# mcu.net
KiCad netlist of a schematic drawn in Altium Designer
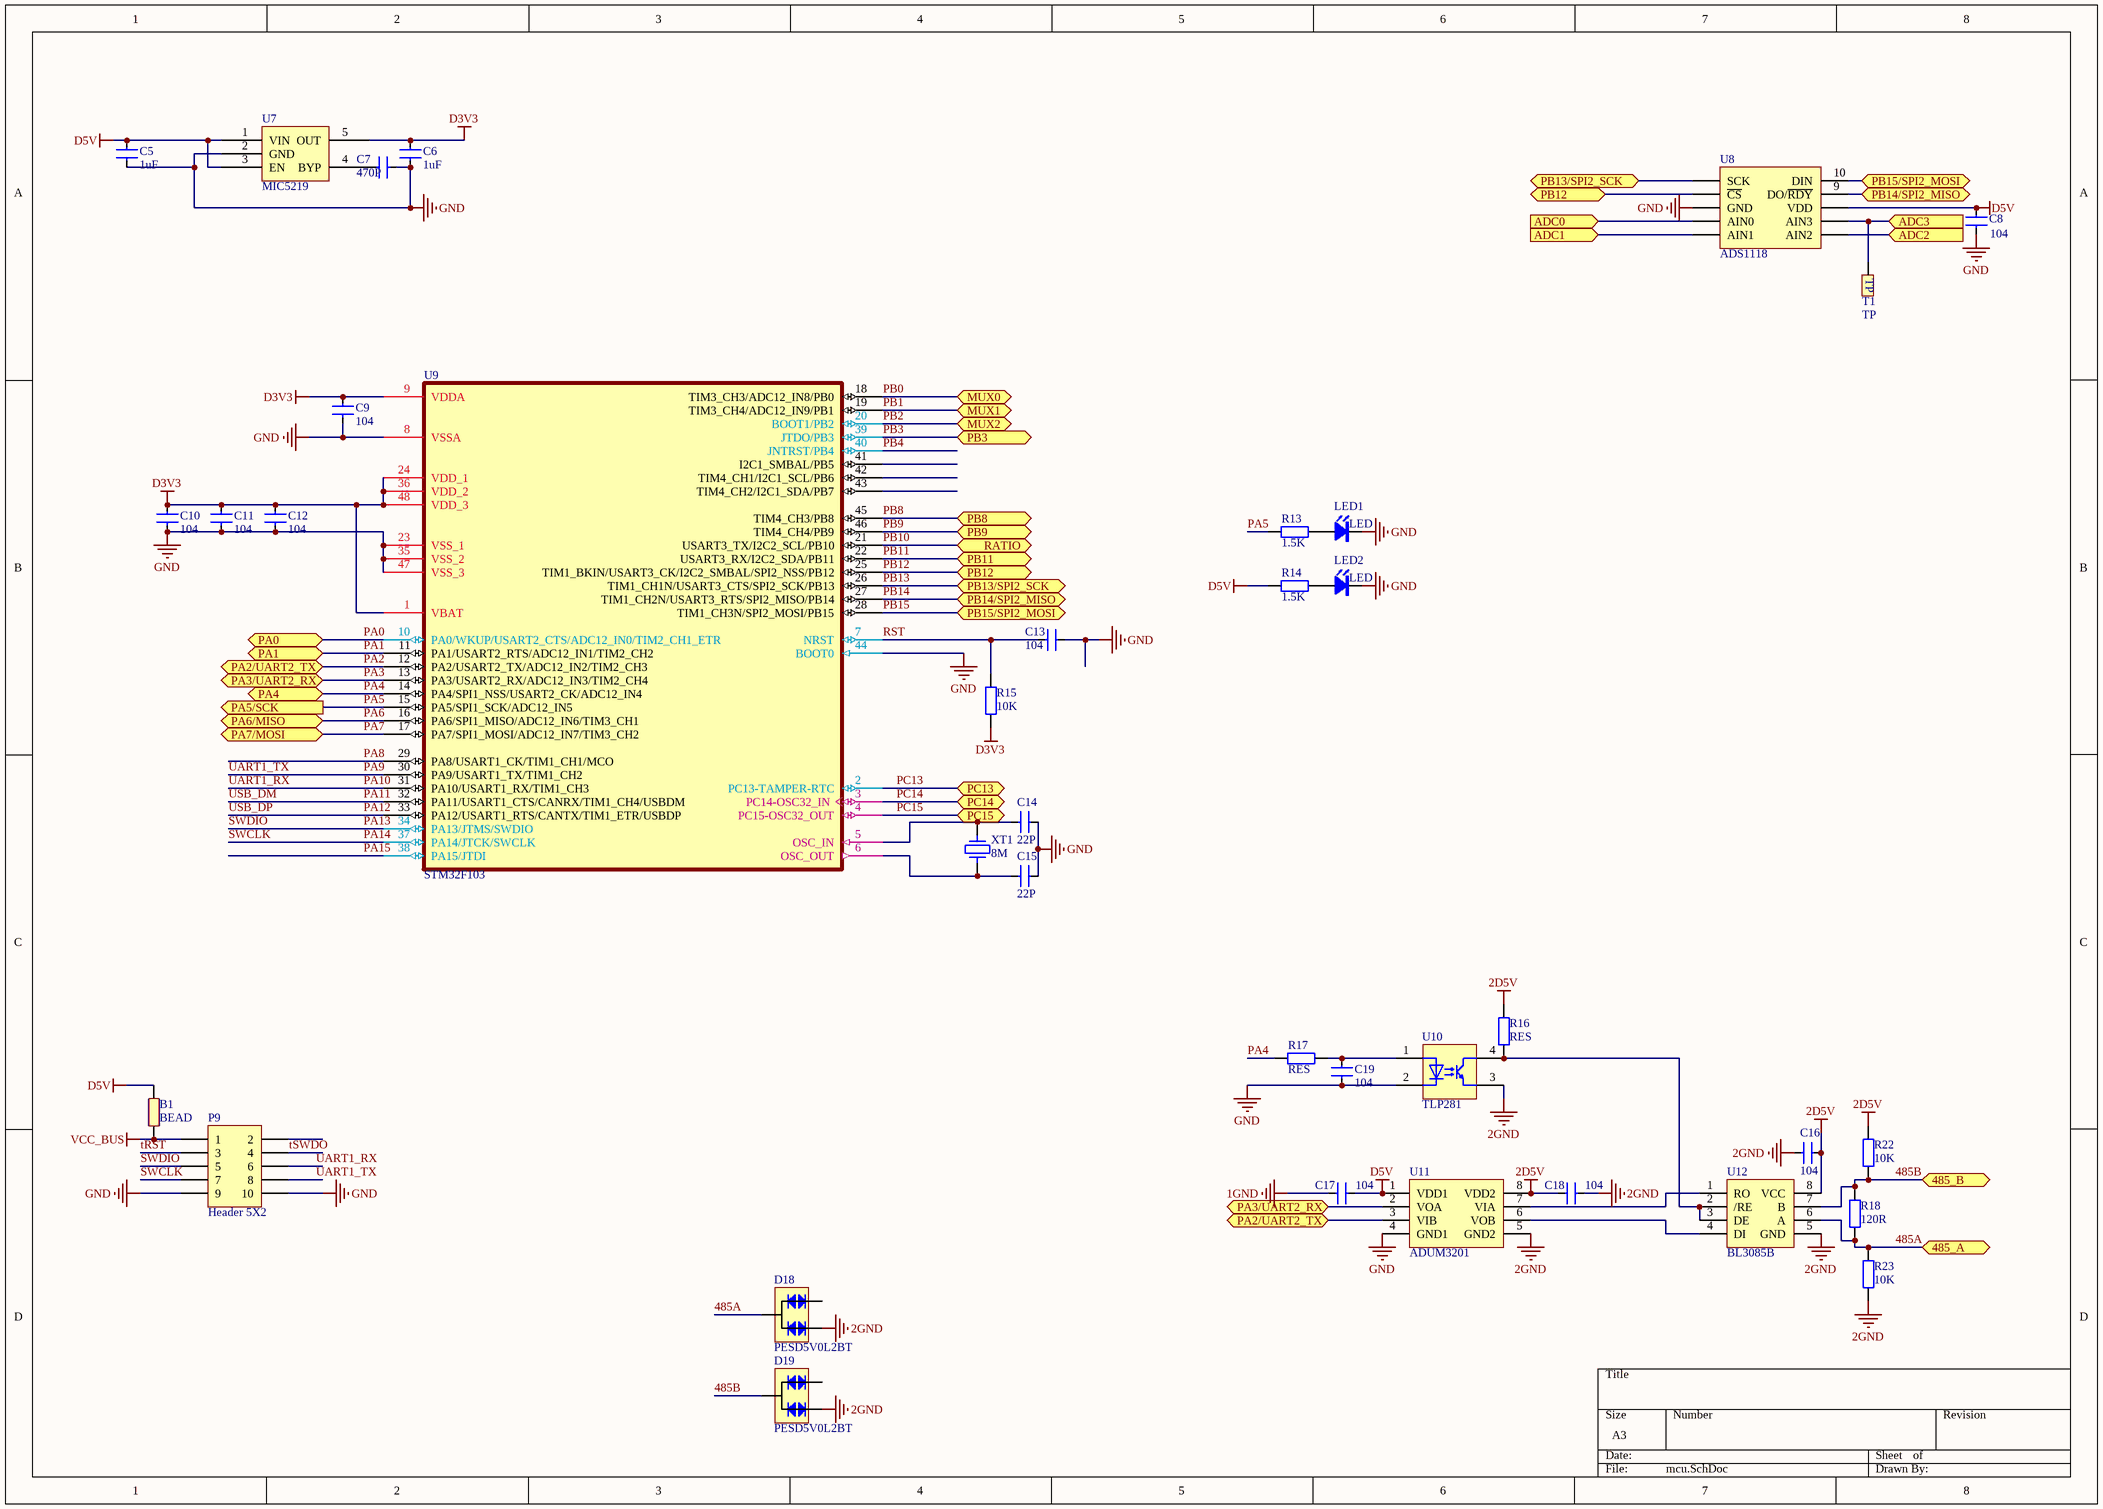
[diagram p0: mcu.SchDoc]

(export (version "E")
  (design (tool "Eeschema 10.0.6"))
  (components
    (comp (ref "B1")
      (value "BEAD")
      (footprint "0603L")
      (description "磁珠")
      (libsource (lib "lib_AD") (part "BEAD"))
    )
    (comp (ref "C5")
      (value "1uF")
      (footprint "0805C")
      (description "普通小电容")
      (libsource (lib "") (part "CAP_1"))
    )
    (comp (ref "C6")
      (value "1uF")
      (footprint "0805C")
      (description "普通小电容")
      (libsource (lib "") (part "CAP_1"))
    )
    (comp (ref "C7")
      (value "470P")
      (footprint "0603C")
      (description "普通小电容")
      (libsource (lib "lib_GMDZ") (part "CAP"))
    )
    (comp (ref "C8")
      (value "104")
      (footprint "0603C")
      (description "普通小电容")
      (libsource (lib "") (part "CAP_1"))
    )
    (comp (ref "C9")
      (value "104")
      (footprint "0603C")
      (description "普通小电容")
      (libsource (lib "lib_GMDZ") (part "CAP"))
    )
    (comp (ref "C10")
      (value "104")
      (footprint "0603C")
      (description "普通小电容")
      (libsource (lib "lib_GMDZ") (part "CAP"))
    )
    (comp (ref "C11")
      (value "104")
      (footprint "0603C")
      (description "普通小电容")
      (libsource (lib "lib_GMDZ") (part "CAP"))
    )
    (comp (ref "C12")
      (value "104")
      (footprint "0603C")
      (description "普通小电容")
      (libsource (lib "lib_GMDZ") (part "CAP"))
    )
    (comp (ref "C13")
      (value "104")
      (footprint "0603C")
      (description "普通小电容")
      (libsource (lib "lib_AD") (part "CAP"))
    )
    (comp (ref "C14")
      (value "22P")
      (footprint "0603C")
      (description "普通小电容")
      (libsource (lib "lib_AD") (part "CAP"))
    )
    (comp (ref "C15")
      (value "22P")
      (footprint "0603C")
      (description "普通小电容")
      (libsource (lib "lib_AD") (part "CAP"))
    )
    (comp (ref "C16")
      (value "104")
      (footprint "0603C")
      (description "普通小电容")
      (libsource (lib "lib_AD") (part "CAP"))
    )
    (comp (ref "C17")
      (value "104")
      (footprint "0603C")
      (description "普通小电容")
      (libsource (lib "lib_AD") (part "CAP"))
    )
    (comp (ref "C18")
      (value "104")
      (footprint "0603C")
      (description "普通小电容")
      (libsource (lib "lib_AD") (part "CAP"))
    )
    (comp (ref "C19")
      (value "104")
      (footprint "0603C")
      (description "普通小电容")
      (libsource (lib "lib_AD") (part "CAP"))
    )
    (comp (ref "D18")
      (value "PESD5V0L2BT")
      (footprint "SOT23A")
      (description "schottky diod")
      (libsource (lib "R_C_L_D") (part "PESD5V0L2BT"))
    )
    (comp (ref "D19")
      (value "PESD5V0L2BT")
      (footprint "SOT23A")
      (description "schottky diod")
      (libsource (lib "R_C_L_D") (part "PESD5V0L2BT"))
    )
    (comp (ref "LED1") (value "LED") (footprint "LED-3") (libsource (lib "lib_AD") (part "LED")))
    (comp (ref "LED2") (value "LED") (footprint "LED-3") (libsource (lib "lib_AD") (part "LED")))
    (comp (ref "P9")
      (value "Header 5X2")
      (footprint "DC2.54-10")
      (description "Header, 5-Pin, Dual row")
      (fields (field (name "PUBLISHER") "Altium Limited"))
      (libsource (lib "Header") (part "Header 5X2"))
    )
    (comp (ref "R13")
      (value "1.5K")
      (footprint "0603R")
      (description "普通电阻")
      (libsource (lib "") (part "RES_1"))
    )
    (comp (ref "R14")
      (value "1.5K")
      (footprint "0603R")
      (description "普通电阻")
      (libsource (lib "") (part "RES_1"))
    )
    (comp (ref "R15")
      (value "10K")
      (footprint "0603R")
      (description "普通电阻")
      (libsource (lib "lib_AD") (part "RES"))
    )
    (comp (ref "R16")
      (value "RES")
      (footprint "0603R")
      (description "普通电阻")
      (libsource (lib "lib_AD") (part "RES"))
    )
    (comp (ref "R17")
      (value "RES")
      (footprint "0603R")
      (description "普通电阻")
      (libsource (lib "") (part "RES_2"))
    )
    (comp (ref "R18")
      (value "120R")
      (footprint "0603R")
      (description "普通电阻")
      (libsource (lib "lib_AD") (part "RES"))
    )
    (comp (ref "R22")
      (value "10K")
      (footprint "0603R")
      (description "普通电阻")
      (libsource (lib "lib_AD") (part "RES"))
    )
    (comp (ref "R23")
      (value "10K")
      (footprint "0603R")
      (description "普通电阻")
      (libsource (lib "lib_AD") (part "RES"))
    )
    (comp (ref "T1")
      (value "TP")
      (footprint "TESTP")
      (description "testpoint")
      (libsource (lib "lib_AD") (part "TP"))
    )
    (comp (ref "U7") (value "MIC5219") (footprint "SOT23-5") (libsource (lib "lib_GMDZ") (part "MIC5219")))
    (comp (ref "U8")
      (value "ADS1118")
      (footprint "TSSOP10")
      (description "16位 ADC")
      (libsource (lib "lib_AD") (part "ADS1118"))
    )
    (comp (ref "U9") (value "STM32F103") (footprint "LQFP48") (libsource (lib "lib_GMDZ") (part "STM32F103")))
    (comp (ref "U10")
      (value "TLP281")
      (footprint "SOP4")
      (description "TLP281 光耦")
      (libsource (lib "lib_AD") (part "TLP281"))
    )
    (comp (ref "U11") (value "ADUM3201") (footprint "SOP8") (libsource (lib "lib_AD") (part "ADUM3201")))
    (comp (ref "U12")
      (value "BL3085B")
      (footprint "SOP8")
      (description "BL3085B 15KV防静电485")
      (libsource (lib "lib_AD") (part "BL3085B"))
    )
    (comp (ref "XT1")
      (value "8M")
      (footprint "5032")
      (description "晶振")
      (libsource (lib "lib_GMDZ") (part "XT"))
    )
  )
  (nets
    (net (code "1") (name "/485A") (class "Default")
      (node (ref "D18") (pin "3") (pinfunction "3_3") (pintype "passive"))
      (node (ref "R18") (pin "1") (pinfunction "1_1") (pintype "passive"))
      (node (ref "R23") (pin "2") (pinfunction "2_2") (pintype "passive"))
      (node (ref "U12") (pin "6") (pinfunction "A_6") (pintype "passive"))
    )
    (net (code "2") (name "/485B") (class "Default")
      (node (ref "D19") (pin "3") (pinfunction "3_3") (pintype "passive"))
      (node (ref "R18") (pin "2") (pinfunction "2_2") (pintype "passive"))
      (node (ref "R22") (pin "1") (pinfunction "1_1") (pintype "passive"))
      (node (ref "U12") (pin "7") (pinfunction "B_7") (pintype "passive"))
    )
    (net (code "3") (name "/ADC0") (class "Default")
      (node (ref "U8") (pin "4") (pinfunction "AIN0_4") (pintype "passive"))
    )
    (net (code "4") (name "/ADC1") (class "Default")
      (node (ref "U8") (pin "5") (pinfunction "AIN1_5") (pintype "passive"))
    )
    (net (code "5") (name "/ADC2") (class "Default")
      (node (ref "U8") (pin "6") (pinfunction "AIN2_6") (pintype "passive"))
    )
    (net (code "6") (name "/ADC3") (class "Default")
      (node (ref "T1") (pin "1") (pinfunction "1_1") (pintype "passive"))
      (node (ref "U8") (pin "7") (pinfunction "AIN3_7") (pintype "passive"))
    )
    (net (code "10") (name "/PA0") (class "Default")
      (node (ref "U9") (pin "10") (pinfunction "PA0/WKUP/USART2_CTS/ADC12_IN0/TIM2_CH1_ETR_10") (pintype "bidirectional"))
    )
    (net (code "11") (name "/PA1") (class "Default")
      (node (ref "U9") (pin "11") (pinfunction "PA1/USART2_RTS/ADC12_IN1/TIM2_CH2_11") (pintype "bidirectional"))
    )
    (net (code "12") (name "/PA2") (class "Default")
      (node (ref "U11") (pin "3") (pinfunction "VIB_3") (pintype "passive"))
      (node (ref "U9") (pin "12") (pinfunction "PA2/USART2_TX/ADC12_IN2/TIM2_CH3_12") (pintype "bidirectional"))
    )
    (net (code "13") (name "/PA3") (class "Default")
      (node (ref "U11") (pin "2") (pinfunction "VOA_2") (pintype "passive"))
      (node (ref "U9") (pin "13") (pinfunction "PA3/USART2_RX/ADC12_IN3/TIM2_CH4_13") (pintype "bidirectional"))
    )
    (net (code "14") (name "/PA4") (class "Default")
      (node (ref "R17") (pin "2") (pinfunction "2_2") (pintype "passive"))
      (node (ref "U9") (pin "14") (pinfunction "PA4/SPI1_NSS/USART2_CK/ADC12_IN4_14") (pintype "bidirectional"))
    )
    (net (code "15") (name "/PA5") (class "Default")
      (node (ref "R13") (pin "1") (pinfunction "1_1") (pintype "passive"))
      (node (ref "U9") (pin "15") (pinfunction "PA5/SPI1_SCK/ADC12_IN5_15") (pintype "bidirectional"))
    )
    (net (code "16") (name "/PA6") (class "Default")
      (node (ref "U9") (pin "16") (pinfunction "PA6/SPI1_MISO/ADC12_IN6/TIM3_CH1_16") (pintype "bidirectional"))
    )
    (net (code "17") (name "/PA7") (class "Default")
      (node (ref "U9") (pin "17") (pinfunction "PA7/SPI1_MOSI/ADC12_IN7/TIM3_CH2_17") (pintype "bidirectional"))
    )
    (net (code "18") (name "/PA8") (class "Default")
      (node (ref "U9") (pin "29") (pinfunction "PA8/USART1_CK/TIM1_CH1/MCO_29") (pintype "bidirectional"))
    )
    (net (code "19") (name "/PA9") (class "Default")
      (node (ref "P9") (pin "8") (pinfunction "8_8") (pintype "passive"))
      (node (ref "U9") (pin "30") (pinfunction "PA9/USART1_TX/TIM1_CH2_30") (pintype "bidirectional"))
    )
    (net (code "20") (name "/PA10") (class "Default")
      (node (ref "P9") (pin "6") (pinfunction "6_6") (pintype "passive"))
      (node (ref "U9") (pin "31") (pinfunction "PA10/USART1_RX/TIM1_CH3_31") (pintype "bidirectional"))
    )
    (net (code "21") (name "/PA11") (class "Default")
      (node (ref "U9") (pin "32") (pinfunction "PA11/USART1_CTS/CANRX/TIM1_CH4/USBDM_32") (pintype "bidirectional"))
    )
    (net (code "22") (name "/PA12") (class "Default")
      (node (ref "U9") (pin "33") (pinfunction "PA12/USART1_RTS/CANTX/TIM1_ETR/USBDP_33") (pintype "bidirectional"))
    )
    (net (code "23") (name "/PA13") (class "Default")
      (node (ref "P9") (pin "5") (pinfunction "5_5") (pintype "passive"))
      (node (ref "U9") (pin "34") (pinfunction "PA13/JTMS/SWDIO_34") (pintype "bidirectional"))
    )
    (net (code "24") (name "/PA14") (class "Default")
      (node (ref "P9") (pin "7") (pinfunction "7_7") (pintype "passive"))
      (node (ref "U9") (pin "37") (pinfunction "PA14/JTCK/SWCLK_37") (pintype "bidirectional"))
    )
    (net (code "25") (name "/PA15") (class "Default")
      (node (ref "U9") (pin "38") (pinfunction "PA15/JTDI_38") (pintype "bidirectional"))
    )
    (net (code "26") (name "/PB0") (class "Default")
      (node (ref "U9") (pin "18") (pinfunction "TIM3_CH3/ADC12_IN8/PB0_18") (pintype "bidirectional"))
    )
    (net (code "27") (name "/PB1") (class "Default")
      (node (ref "U9") (pin "19") (pinfunction "TIM3_CH4/ADC12_IN9/PB1_19") (pintype "bidirectional"))
    )
    (net (code "28") (name "/PB2") (class "Default")
      (node (ref "U9") (pin "20") (pinfunction "BOOT1/PB2_20") (pintype "bidirectional"))
    )
    (net (code "29") (name "/PB3") (class "Default")
      (node (ref "U9") (pin "39") (pinfunction "JTDO/PB3_39") (pintype "bidirectional"))
    )
    (net (code "30") (name "/PB4") (class "Default")
      (node (ref "U9") (pin "40") (pinfunction "JNTRST/PB4_40") (pintype "bidirectional"))
    )
    (net (code "31") (name "/PB8") (class "Default")
      (node (ref "U9") (pin "45") (pinfunction "TIM4_CH3/PB8_45") (pintype "bidirectional"))
    )
    (net (code "32") (name "/PB9") (class "Default")
      (node (ref "U9") (pin "46") (pinfunction "TIM4_CH4/PB9_46") (pintype "bidirectional"))
    )
    (net (code "33") (name "/PB10") (class "Default")
      (node (ref "U9") (pin "21") (pinfunction "USART3_TX/I2C2_SCL/PB10_21") (pintype "bidirectional"))
    )
    (net (code "34") (name "/PB11") (class "Default")
      (node (ref "U9") (pin "22") (pinfunction "USART3_RX/I2C2_SDA/PB11_22") (pintype "bidirectional"))
    )
    (net (code "35") (name "/PB12") (class "Default")
      (node (ref "U8") (pin "2") (pinfunction "~{CS}_2") (pintype "passive"))
      (node (ref "U9") (pin "25") (pinfunction "TIM1_BKIN/USART3_CK/I2C2_SMBAL/SPI2_NSS/PB12_25") (pintype "bidirectional"))
    )
    (net (code "36") (name "/PB13") (class "Default")
      (node (ref "U8") (pin "1") (pinfunction "SCK_1") (pintype "passive"))
      (node (ref "U9") (pin "26") (pinfunction "TIM1_CH1N/USART3_CTS/SPI2_SCK/PB13_26") (pintype "bidirectional"))
    )
    (net (code "37") (name "/PB14") (class "Default")
      (node (ref "U8") (pin "9") (pinfunction "DO/~{RDY}_9") (pintype "passive"))
      (node (ref "U9") (pin "27") (pinfunction "TIM1_CH2N/USART3_RTS/SPI2_MISO/PB14_27") (pintype "bidirectional"))
    )
    (net (code "38") (name "/PB15") (class "Default")
      (node (ref "U8") (pin "10") (pinfunction "DIN_10") (pintype "passive"))
      (node (ref "U9") (pin "28") (pinfunction "TIM1_CH3N/SPI2_MOSI/PB15_28") (pintype "bidirectional"))
    )
    (net (code "39") (name "/PC13") (class "Default")
      (node (ref "U9") (pin "2") (pinfunction "PC13-TAMPER-RTC_2") (pintype "bidirectional"))
    )
    (net (code "40") (name "/PC14") (class "Default")
      (node (ref "U9") (pin "3") (pinfunction "PC14-OSC32_IN_3") (pintype "bidirectional"))
    )
    (net (code "41") (name "/PC15") (class "Default")
      (node (ref "U9") (pin "4") (pinfunction "PC15-OSC32_OUT_4") (pintype "bidirectional"))
    )
    (net (code "42") (name "/RST") (class "Default")
      (node (ref "C13") (pin "1") (pinfunction "1_1") (pintype "passive"))
      (node (ref "R15") (pin "2") (pinfunction "2_2") (pintype "passive"))
      (node (ref "U9") (pin "7") (pinfunction "NRST_7") (pintype "bidirectional"))
    )
    (net (code "43") (name "/tRST") (class "Default")
      (node (ref "P9") (pin "3") (pinfunction "3_3") (pintype "passive"))
    )
    (net (code "44") (name "/tSWDO") (class "Default")
      (node (ref "P9") (pin "4") (pinfunction "4_4") (pintype "passive"))
    )
    (net (code "45") (name "1GND") (class "Default")
      (node (ref "C17") (pin "2") (pinfunction "2_2") (pintype "passive"))
    )
    (net (code "46") (name "2D5V") (class "Default")
      (node (ref "C16") (pin "2") (pinfunction "2_2") (pintype "passive"))
      (node (ref "C18") (pin "2") (pinfunction "2_2") (pintype "passive"))
      (node (ref "R16") (pin "2") (pinfunction "2_2") (pintype "passive"))
      (node (ref "R22") (pin "2") (pinfunction "2_2") (pintype "passive"))
      (node (ref "U11") (pin "8") (pinfunction "VDD2_8") (pintype "passive"))
      (node (ref "U12") (pin "8") (pinfunction "VCC_8") (pintype "passive"))
    )
    (net (code "47") (name "2GND") (class "Default")
      (node (ref "C16") (pin "1") (pinfunction "1_1") (pintype "passive"))
      (node (ref "C18") (pin "1") (pinfunction "1_1") (pintype "passive"))
      (node (ref "D18") (pin "1") (pinfunction "1_1") (pintype "passive"))
      (node (ref "D19") (pin "1") (pinfunction "1_1") (pintype "passive"))
      (node (ref "R23") (pin "1") (pinfunction "1_1") (pintype "passive"))
      (node (ref "U10") (pin "3") (pinfunction "3_3") (pintype "passive"))
      (node (ref "U11") (pin "5") (pinfunction "GND2_5") (pintype "passive"))
      (node (ref "U12") (pin "5") (pinfunction "GND_5") (pintype "passive"))
    )
    (net (code "48") (name "D3V3") (class "Default")
      (node (ref "C10") (pin "2") (pinfunction "2_2") (pintype "passive"))
      (node (ref "C11") (pin "1") (pinfunction "1_1") (pintype "passive"))
      (node (ref "C12") (pin "2") (pinfunction "2_2") (pintype "passive"))
      (node (ref "C6") (pin "2") (pinfunction "2_2") (pintype "passive"))
      (node (ref "C9") (pin "2") (pinfunction "2_2") (pintype "passive"))
      (node (ref "R15") (pin "1") (pinfunction "1_1") (pintype "passive"))
      (node (ref "U7") (pin "5") (pinfunction "OUT_5") (pintype "passive"))
      (node (ref "U9") (pin "1") (pinfunction "VBAT_1") (pintype "power_in"))
      (node (ref "U9") (pin "24") (pinfunction "VDD_1_24") (pintype "power_in"))
      (node (ref "U9") (pin "36") (pinfunction "VDD_2_36") (pintype "power_in"))
      (node (ref "U9") (pin "48") (pinfunction "VDD_3_48") (pintype "power_in"))
      (node (ref "U9") (pin "9") (pinfunction "VDDA_9") (pintype "power_in"))
    )
    (net (code "49") (name "D5V") (class "Default")
      (node (ref "B1") (pin "2") (pinfunction "2_2") (pintype "passive"))
      (node (ref "C17") (pin "1") (pinfunction "1_1") (pintype "passive"))
      (node (ref "C5") (pin "2") (pinfunction "2_2") (pintype "passive"))
      (node (ref "C8") (pin "2") (pinfunction "2_2") (pintype "passive"))
      (node (ref "R14") (pin "1") (pinfunction "1_1") (pintype "passive"))
      (node (ref "U11") (pin "1") (pinfunction "VDD1_1") (pintype "passive"))
      (node (ref "U7") (pin "1") (pinfunction "VIN_1") (pintype "passive"))
      (node (ref "U7") (pin "3") (pinfunction "EN_3") (pintype "passive"))
      (node (ref "U8") (pin "8") (pinfunction "VDD_8") (pintype "passive"))
    )
    (net (code "50") (name "GND") (class "Default")
      (node (ref "C10") (pin "1") (pinfunction "1_1") (pintype "passive"))
      (node (ref "C11") (pin "2") (pinfunction "2_2") (pintype "passive"))
      (node (ref "C12") (pin "1") (pinfunction "1_1") (pintype "passive"))
      (node (ref "C13") (pin "2") (pinfunction "2_2") (pintype "passive"))
      (node (ref "C14") (pin "2") (pinfunction "2_2") (pintype "passive"))
      (node (ref "C15") (pin "2") (pinfunction "2_2") (pintype "passive"))
      (node (ref "C19") (pin "2") (pinfunction "2_2") (pintype "passive"))
      (node (ref "C5") (pin "1") (pinfunction "1_1") (pintype "passive"))
      (node (ref "C6") (pin "1") (pinfunction "1_1") (pintype "passive"))
      (node (ref "C7") (pin "2") (pinfunction "2_2") (pintype "passive"))
      (node (ref "C8") (pin "1") (pinfunction "1_1") (pintype "passive"))
      (node (ref "C9") (pin "1") (pinfunction "1_1") (pintype "passive"))
      (node (ref "LED1") (pin "K") (pinfunction "2_K") (pintype "passive"))
      (node (ref "LED2") (pin "K") (pinfunction "2_K") (pintype "passive"))
      (node (ref "P9") (pin "10") (pinfunction "10_10") (pintype "passive"))
      (node (ref "P9") (pin "9") (pinfunction "9_9") (pintype "passive"))
      (node (ref "U10") (pin "2") (pinfunction "2_2") (pintype "passive"))
      (node (ref "U11") (pin "4") (pinfunction "GND1_4") (pintype "passive"))
      (node (ref "U7") (pin "2") (pinfunction "GND_2") (pintype "passive"))
      (node (ref "U8") (pin "3") (pinfunction "GND_3") (pintype "passive"))
      (node (ref "U9") (pin "23") (pinfunction "VSS_1_23") (pintype "power_in"))
      (node (ref "U9") (pin "35") (pinfunction "VSS_2_35") (pintype "power_in"))
      (node (ref "U9") (pin "44") (pinfunction "BOOT0_44") (pintype "input"))
      (node (ref "U9") (pin "47") (pinfunction "VSS_3_47") (pintype "power_in"))
      (node (ref "U9") (pin "8") (pinfunction "VSSA_8") (pintype "power_in"))
    )
    (net (code "51") (name "Net-(C19-Pad1)") (class "Default")
      (node (ref "C19") (pin "1") (pinfunction "1_1") (pintype "passive"))
      (node (ref "R17") (pin "1") (pinfunction "1_1") (pintype "passive"))
      (node (ref "U10") (pin "1") (pinfunction "1_1") (pintype "passive"))
    )
    (net (code "52") (name "Net-(LED1-1)") (class "Default")
      (node (ref "LED1") (pin "A") (pinfunction "1_A") (pintype "passive"))
      (node (ref "R13") (pin "2") (pinfunction "2_2") (pintype "passive"))
    )
    (net (code "53") (name "Net-(LED2-1)") (class "Default")
      (node (ref "LED2") (pin "A") (pinfunction "1_A") (pintype "passive"))
      (node (ref "R14") (pin "2") (pinfunction "2_2") (pintype "passive"))
    )
    (net (code "54") (name "Net-(U7-BYP)") (class "Default")
      (node (ref "C7") (pin "1") (pinfunction "1_1") (pintype "passive"))
      (node (ref "U7") (pin "4") (pinfunction "BYP_4") (pintype "passive"))
    )
    (net (code "55") (name "Net-(U9-OSC_IN)") (class "Default")
      (node (ref "C14") (pin "1") (pinfunction "1_1") (pintype "passive"))
      (node (ref "U9") (pin "5") (pinfunction "OSC_IN_5") (pintype "input"))
      (node (ref "XT1") (pin "1") (pinfunction "1_1") (pintype "passive"))
    )
    (net (code "56") (name "Net-(U9-OSC_OUT)") (class "Default")
      (node (ref "C15") (pin "1") (pinfunction "1_1") (pintype "passive"))
      (node (ref "U9") (pin "6") (pinfunction "OSC_OUT_6") (pintype "output"))
      (node (ref "XT1") (pin "2") (pinfunction "2_2") (pintype "passive"))
    )
    (net (code "57") (name "Net-(U11-VIA)") (class "Default")
      (node (ref "U11") (pin "7") (pinfunction "VIA_7") (pintype "passive"))
      (node (ref "U12") (pin "1") (pinfunction "RO_1") (pintype "passive"))
    )
    (net (code "58") (name "Net-(U11-VOB)") (class "Default")
      (node (ref "U11") (pin "6") (pinfunction "VOB_6") (pintype "passive"))
      (node (ref "U12") (pin "4") (pinfunction "DI_4") (pintype "passive"))
    )
    (net (code "59") (name "Net-(U12-DE)") (class "Default")
      (node (ref "R16") (pin "1") (pinfunction "1_1") (pintype "passive"))
      (node (ref "U10") (pin "4") (pinfunction "4_4") (pintype "passive"))
      (node (ref "U12") (pin "2") (pinfunction "/RE_2") (pintype "passive"))
      (node (ref "U12") (pin "3") (pinfunction "DE_3") (pintype "passive"))
    )
    (net (code "60") (name "VCC_BUS") (class "Default")
      (node (ref "B1") (pin "1") (pinfunction "1_1") (pintype "passive"))
      (node (ref "P9") (pin "1") (pinfunction "1_1") (pintype "passive"))
    )
    (net (code "61") (name "unconnected-(D18-Pad2)") (class "Default")
      (node (ref "D18") (pin "2") (pinfunction "2_2") (pintype "passive"))
    )
    (net (code "62") (name "unconnected-(D19-Pad2)") (class "Default")
      (node (ref "D19") (pin "2") (pinfunction "2_2") (pintype "passive"))
    )
    (net (code "63") (name "unconnected-(P9-Pad2)") (class "Default")
      (node (ref "P9") (pin "2") (pinfunction "2_2") (pintype "passive"))
    )
    (net (code "64") (name "unconnected-(U9-I2C1_SMBAL{slash}PB5-Pad41)") (class "Default")
      (node (ref "U9") (pin "41") (pinfunction "I2C1_SMBAL/PB5_41") (pintype "bidirectional"))
    )
    (net (code "65") (name "unconnected-(U9-TIM4_CH1{slash}I2C1_SCL{slash}PB6-Pad42)") (class "Default")
      (node (ref "U9") (pin "42") (pinfunction "TIM4_CH1/I2C1_SCL/PB6_42") (pintype "bidirectional"))
    )
    (net (code "66") (name "unconnected-(U9-TIM4_CH2{slash}I2C1_SDA{slash}PB7-Pad43)") (class "Default")
      (node (ref "U9") (pin "43") (pinfunction "TIM4_CH2/I2C1_SDA/PB7_43") (pintype "bidirectional"))
    )
  )
)
